# IF_RX.net
KiCad netlist of a schematic drawn in Altium Designer
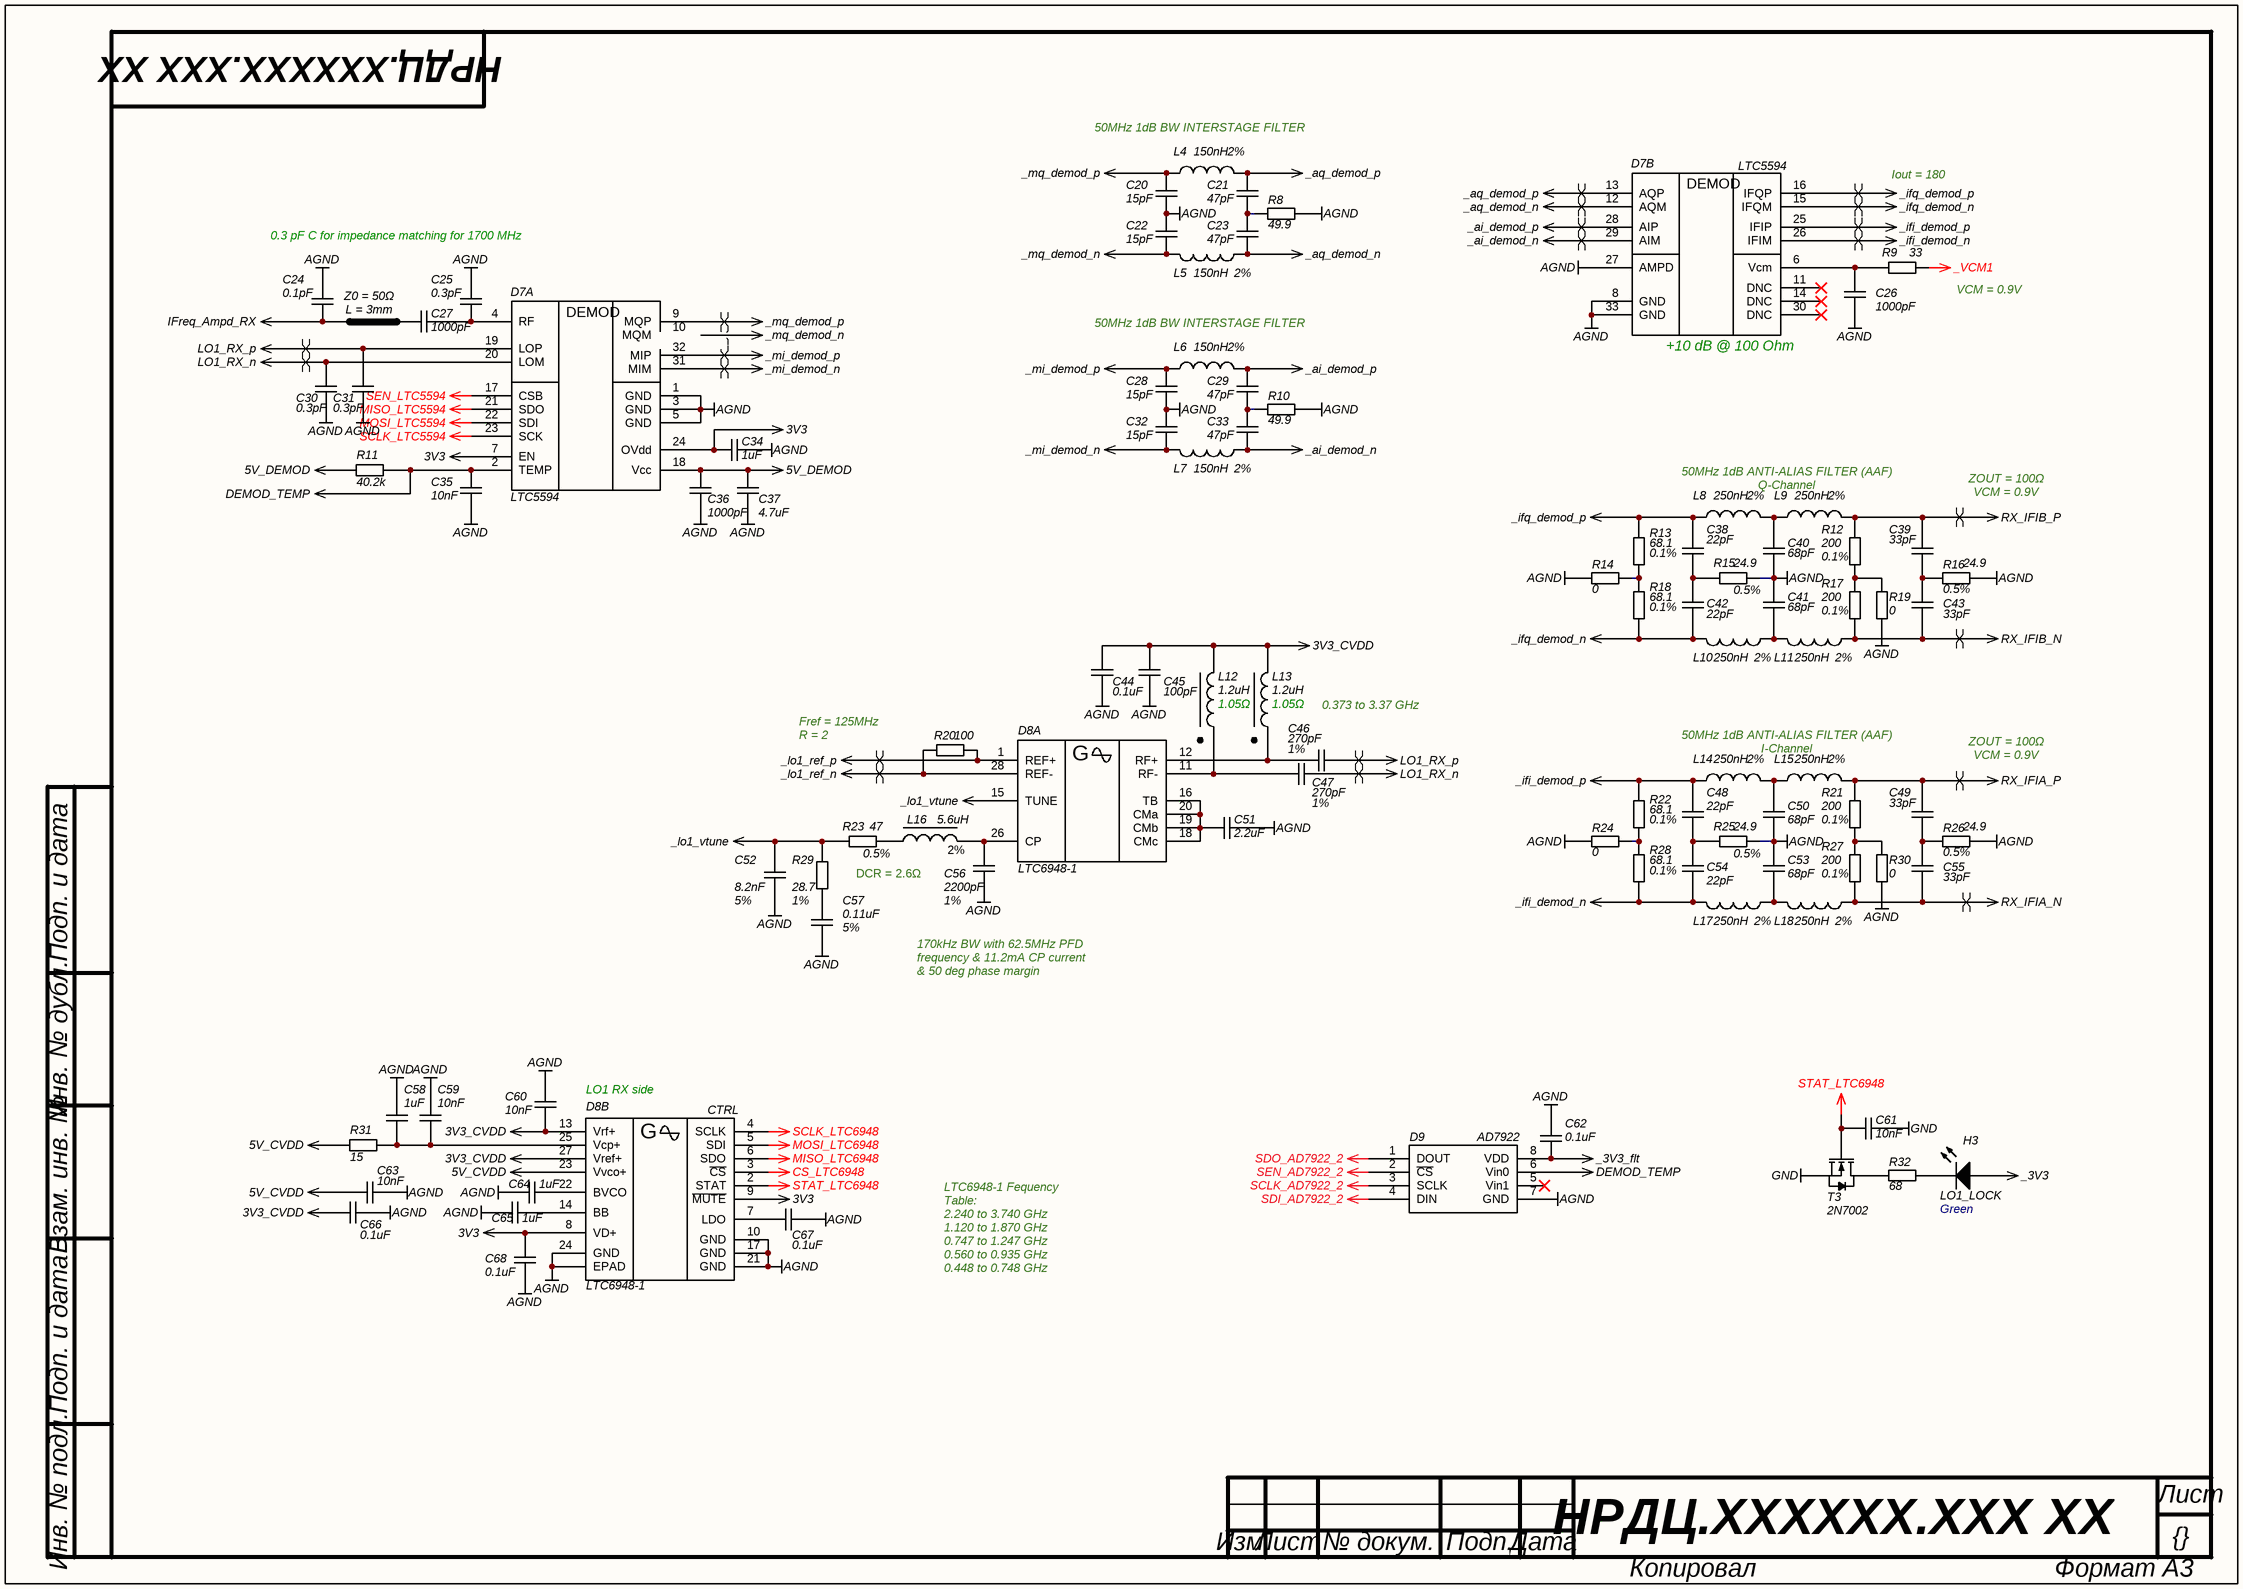
[diagram p0: IF_RX.SchDoc]

(export (version "E")
  (design (tool "Eeschema 10.0.6"))
  (components
    (comp (ref "C20")
      (value "15pF")
      (footprint "C0402")
      (description "SMD Capacitor")
      (fields (field (name "MANUFACTURER") "Murata") (field (name "TOLERANCE") "1%"))
      (libsource (lib "Kintex_SDR") (part "CAP"))
    )
    (comp (ref "C21")
      (value "47pF")
      (footprint "C0402")
      (description "SMD Capacitor")
      (fields (field (name "MANUFACTURER") "Murata") (field (name "TOLERANCE") "1%"))
      (libsource (lib "Kintex_SDR") (part "CAP"))
    )
    (comp (ref "C22")
      (value "15pF")
      (footprint "C0402")
      (description "SMD Capacitor")
      (fields (field (name "MANUFACTURER") "Murata") (field (name "TOLERANCE") "1%"))
      (libsource (lib "Kintex_SDR") (part "CAP"))
    )
    (comp (ref "C23")
      (value "47pF")
      (footprint "C0402")
      (description "SMD Capacitor")
      (fields (field (name "MANUFACTURER") "Murata") (field (name "TOLERANCE") "1%"))
      (libsource (lib "Kintex_SDR") (part "CAP"))
    )
    (comp (ref "C24")
      (value "0.1pF")
      (footprint "C0402")
      (description "SMD Capacitor")
      (fields (field (name "MANUFACTURER") "Murata") (field (name "TOLERANCE") "±0.05pF"))
      (libsource (lib "Kintex_SDR") (part "CAP"))
    )
    (comp (ref "C25")
      (value "0.3pF")
      (footprint "C0402")
      (description "SMD Capacitor")
      (fields (field (name "MANUFACTURER") "Murata") (field (name "TOLERANCE") "±0.05pF"))
      (libsource (lib "Kintex_SDR") (part "CAP"))
    )
    (comp (ref "C26")
      (value "1000pF")
      (footprint "C0402")
      (description "SMD Capacitor")
      (fields (field (name "MANUFACTURER") "Murata") (field (name "TOLERANCE") "5%"))
      (libsource (lib "Kintex_SDR") (part "CAP"))
    )
    (comp (ref "C27")
      (value "1000pF")
      (footprint "C0402")
      (description "SMD Capacitor")
      (fields (field (name "MANUFACTURER") "Murata") (field (name "TOLERANCE") "5%"))
      (libsource (lib "Kintex_SDR") (part "CAP"))
    )
    (comp (ref "C28")
      (value "15pF")
      (footprint "C0402")
      (description "SMD Capacitor")
      (fields (field (name "MANUFACTURER") "Murata") (field (name "TOLERANCE") "1%"))
      (libsource (lib "Kintex_SDR") (part "CAP"))
    )
    (comp (ref "C29")
      (value "47pF")
      (footprint "C0402")
      (description "SMD Capacitor")
      (fields (field (name "MANUFACTURER") "Murata") (field (name "TOLERANCE") "1%"))
      (libsource (lib "Kintex_SDR") (part "CAP"))
    )
    (comp (ref "C30")
      (value "0.3pF")
      (footprint "C0402")
      (description "SMD Capacitor")
      (fields (field (name "MANUFACTURER") "Murata") (field (name "TOLERANCE") "±0.05pF"))
      (libsource (lib "Kintex_SDR") (part "CAP"))
    )
    (comp (ref "C31")
      (value "0.3pF")
      (footprint "C0402")
      (description "SMD Capacitor")
      (fields (field (name "MANUFACTURER") "Murata") (field (name "TOLERANCE") "±0.05pF"))
      (libsource (lib "Kintex_SDR") (part "CAP"))
    )
    (comp (ref "C32")
      (value "15pF")
      (footprint "C0402")
      (description "SMD Capacitor")
      (fields (field (name "MANUFACTURER") "Murata") (field (name "TOLERANCE") "1%"))
      (libsource (lib "Kintex_SDR") (part "CAP"))
    )
    (comp (ref "C33")
      (value "47pF")
      (footprint "C0402")
      (description "SMD Capacitor")
      (fields (field (name "MANUFACTURER") "Murata") (field (name "TOLERANCE") "1%"))
      (libsource (lib "Kintex_SDR") (part "CAP"))
    )
    (comp (ref "C34")
      (value "1uF")
      (footprint "C0805")
      (description "SMD Capacitor")
      (fields (field (name "MANUFACTURER") "Murata") (field (name "TOLERANCE") "10%"))
      (libsource (lib "Kintex_SDR") (part "CAP"))
    )
    (comp (ref "C35")
      (value "10nF")
      (footprint "C0402")
      (description "SMD Capacitor")
      (fields (field (name "MANUFACTURER") "Murata") (field (name "TOLERANCE") "10%"))
      (libsource (lib "Kintex_SDR") (part "CAP"))
    )
    (comp (ref "C36")
      (value "1000pF")
      (footprint "C0402")
      (description "SMD Capacitor")
      (fields (field (name "MANUFACTURER") "Murata") (field (name "TOLERANCE") "5%"))
      (libsource (lib "Kintex_SDR") (part "CAP"))
    )
    (comp (ref "C37")
      (value "4.7uF")
      (footprint "C0805")
      (description "SMD Capacitor")
      (fields (field (name "MANUFACTURER") "Murata") (field (name "TOLERANCE") "10%"))
      (libsource (lib "Kintex_SDR") (part "CAP"))
    )
    (comp (ref "C38")
      (value "22pF")
      (footprint "C0402")
      (description "SMD Capacitor")
      (fields (field (name "MANUFACTURER") "Murata") (field (name "TOLERANCE") "1%"))
      (libsource (lib "Kintex_SDR") (part "CAP"))
    )
    (comp (ref "C39")
      (value "33pF")
      (footprint "C0402")
      (description "SMD Capacitor")
      (fields (field (name "MANUFACTURER") "Murata") (field (name "TOLERANCE") "1%"))
      (libsource (lib "Kintex_SDR") (part "CAP"))
    )
    (comp (ref "C40")
      (value "68pF")
      (footprint "C0402")
      (description "SMD Capacitor")
      (fields (field (name "MANUFACTURER") "Murata") (field (name "TOLERANCE") "1%"))
      (libsource (lib "Kintex_SDR") (part "CAP"))
    )
    (comp (ref "C41")
      (value "68pF")
      (footprint "C0402")
      (description "SMD Capacitor")
      (fields (field (name "MANUFACTURER") "Murata") (field (name "TOLERANCE") "1%"))
      (libsource (lib "Kintex_SDR") (part "CAP"))
    )
    (comp (ref "C42")
      (value "22pF")
      (footprint "C0402")
      (description "SMD Capacitor")
      (fields (field (name "MANUFACTURER") "Murata") (field (name "TOLERANCE") "1%"))
      (libsource (lib "Kintex_SDR") (part "CAP"))
    )
    (comp (ref "C43")
      (value "33pF")
      (footprint "C0402")
      (description "SMD Capacitor")
      (fields (field (name "MANUFACTURER") "Murata") (field (name "TOLERANCE") "1%"))
      (libsource (lib "Kintex_SDR") (part "CAP"))
    )
    (comp (ref "C44")
      (value "0.1uF")
      (footprint "C0402")
      (description "SMD Capacitor")
      (fields (field (name "MANUFACTURER") "Murata") (field (name "TOLERANCE") "10%"))
      (libsource (lib "Kintex_SDR") (part "CAP"))
    )
    (comp (ref "C45")
      (value "100pF")
      (footprint "C0402")
      (description "SMD Capacitor")
      (fields (field (name "MANUFACTURER") "Murata") (field (name "TOLERANCE") "1%"))
      (libsource (lib "Kintex_SDR") (part "CAP"))
    )
    (comp (ref "C46")
      (value "270pF")
      (footprint "C0402")
      (description "SMD Capacitor")
      (fields
        (field (name "MANUFACTURER") "Murata")
        (field (name "TOLERANCE") "1%")
        (field (name "VOLTAGE") "50V")
      )
      (libsource (lib "Kintex_SDR") (part "CAP"))
    )
    (comp (ref "C47")
      (value "270pF")
      (footprint "C0402")
      (description "SMD Capacitor")
      (fields
        (field (name "MANUFACTURER") "Murata")
        (field (name "TOLERANCE") "1%")
        (field (name "VOLTAGE") "50V")
      )
      (libsource (lib "Kintex_SDR") (part "CAP"))
    )
    (comp (ref "C48")
      (value "22pF")
      (footprint "C0402")
      (description "SMD Capacitor")
      (fields (field (name "MANUFACTURER") "Murata") (field (name "TOLERANCE") "1%"))
      (libsource (lib "Kintex_SDR") (part "CAP"))
    )
    (comp (ref "C49")
      (value "33pF")
      (footprint "C0402")
      (description "SMD Capacitor")
      (fields (field (name "MANUFACTURER") "Murata") (field (name "TOLERANCE") "1%"))
      (libsource (lib "Kintex_SDR") (part "CAP"))
    )
    (comp (ref "C50")
      (value "68pF")
      (footprint "C0402")
      (description "SMD Capacitor")
      (fields (field (name "MANUFACTURER") "Murata") (field (name "TOLERANCE") "1%"))
      (libsource (lib "Kintex_SDR") (part "CAP"))
    )
    (comp (ref "C51")
      (value "2.2uF")
      (footprint "C0603")
      (description "SMD Capacitor")
      (fields (field (name "MANUFACTURER") "Murata") (field (name "TOLERANCE") "10%"))
      (libsource (lib "Kintex_SDR") (part "CAP"))
    )
    (comp (ref "C52")
      (value "8.2nF")
      (footprint "C0603")
      (description "SMD Capacitor")
      (fields
        (field (name "MANUFACTURER") "Murata")
        (field (name "TOLERANCE") "5%")
        (field (name "VOLTAGE") "50V")
      )
      (libsource (lib "Kintex_SDR") (part "CAP"))
    )
    (comp (ref "C53")
      (value "68pF")
      (footprint "C0402")
      (description "SMD Capacitor")
      (fields (field (name "MANUFACTURER") "Murata") (field (name "TOLERANCE") "1%"))
      (libsource (lib "Kintex_SDR") (part "CAP"))
    )
    (comp (ref "C54")
      (value "22pF")
      (footprint "C0402")
      (description "SMD Capacitor")
      (fields (field (name "MANUFACTURER") "Murata") (field (name "TOLERANCE") "1%"))
      (libsource (lib "Kintex_SDR") (part "CAP"))
    )
    (comp (ref "C55")
      (value "33pF")
      (footprint "C0402")
      (description "SMD Capacitor")
      (fields (field (name "MANUFACTURER") "Murata") (field (name "TOLERANCE") "1%"))
      (libsource (lib "Kintex_SDR") (part "CAP"))
    )
    (comp (ref "C56")
      (value "2200pF")
      (footprint "C0603")
      (description "SMD Capacitor")
      (fields
        (field (name "MANUFACTURER") "Murata")
        (field (name "TOLERANCE") "1%")
        (field (name "VOLTAGE") "50V")
      )
      (libsource (lib "Kintex_SDR") (part "CAP"))
    )
    (comp (ref "C57")
      (value "0.11uF")
      (footprint "C0805")
      (description "SMD Capacitor")
      (fields
        (field (name "MANUFACTURER") "Murata")
        (field (name "TOLERANCE") "5%")
        (field (name "VOLTAGE") "50V")
      )
      (libsource (lib "Kintex_SDR") (part "CAP"))
    )
    (comp (ref "C58")
      (value "1uF")
      (footprint "C0805")
      (description "SMD Capacitor")
      (fields (field (name "MANUFACTURER") "Murata") (field (name "TOLERANCE") "10%"))
      (libsource (lib "Kintex_SDR") (part "CAP"))
    )
    (comp (ref "C59")
      (value "10nF")
      (footprint "C0402")
      (description "SMD Capacitor")
      (fields (field (name "MANUFACTURER") "Murata") (field (name "TOLERANCE") "10%"))
      (libsource (lib "Kintex_SDR") (part "CAP"))
    )
    (comp (ref "C60")
      (value "10nF")
      (footprint "C0402")
      (description "SMD Capacitor")
      (fields (field (name "MANUFACTURER") "Murata") (field (name "TOLERANCE") "10%"))
      (libsource (lib "Kintex_SDR") (part "CAP"))
    )
    (comp (ref "C61")
      (value "10nF")
      (footprint "C0402")
      (description "SMD Capacitor")
      (fields (field (name "MANUFACTURER") "Murata") (field (name "TOLERANCE") "10%"))
      (libsource (lib "Kintex_SDR") (part "CAP"))
    )
    (comp (ref "C62")
      (value "0.1uF")
      (footprint "C0402")
      (description "SMD Capacitor")
      (fields (field (name "MANUFACTURER") "Murata") (field (name "TOLERANCE") "10%"))
      (libsource (lib "Kintex_SDR") (part "CAP"))
    )
    (comp (ref "C63")
      (value "10nF")
      (footprint "C0402")
      (description "SMD Capacitor")
      (fields (field (name "MANUFACTURER") "Murata") (field (name "TOLERANCE") "10%"))
      (libsource (lib "Kintex_SDR") (part "CAP"))
    )
    (comp (ref "C64")
      (value "1uF")
      (footprint "C0805")
      (description "SMD Capacitor")
      (fields (field (name "MANUFACTURER") "Murata") (field (name "TOLERANCE") "10%"))
      (libsource (lib "Kintex_SDR") (part "CAP"))
    )
    (comp (ref "C65")
      (value "1uF")
      (footprint "C0805")
      (description "SMD Capacitor")
      (fields (field (name "MANUFACTURER") "Murata") (field (name "TOLERANCE") "10%"))
      (libsource (lib "Kintex_SDR") (part "CAP"))
    )
    (comp (ref "C66")
      (value "0.1uF")
      (footprint "C0402")
      (description "SMD Capacitor")
      (fields (field (name "MANUFACTURER") "Murata") (field (name "TOLERANCE") "10%"))
      (libsource (lib "Kintex_SDR") (part "CAP"))
    )
    (comp (ref "C67")
      (value "0.1uF")
      (footprint "C0402")
      (description "SMD Capacitor")
      (fields (field (name "MANUFACTURER") "Murata") (field (name "TOLERANCE") "10%"))
      (libsource (lib "Kintex_SDR") (part "CAP"))
    )
    (comp (ref "C68")
      (value "0.1uF")
      (footprint "C0402")
      (description "SMD Capacitor")
      (fields (field (name "MANUFACTURER") "Murata") (field (name "TOLERANCE") "10%"))
      (libsource (lib "Kintex_SDR") (part "CAP"))
    )
    (comp (ref "D7")
      (value "LTC5594")
      (footprint "DBLib:QFN-32")
      (description "Quadrature Demodulator")
      (fields (field (name "MANUFACTURER") "Analog Devices"))
      (libsource (lib "DBLib") (part "LTC5594"))
    )
    (comp (ref "D8")
      (value "LTC6948-1")
      (footprint "QFN-28")
      (description "The LTC®LTC6948 is a high performance, low noise, 6.39GHz  phase-locked loop (PLL)")
      (fields (field (name "MANUFACTURER") "Linear Technology") (field (name "VOLTAGE") "3.15 V ~ 5.25 V"))
      (libsource (lib "") (part "LTC6948_1"))
    )
    (comp (ref "D9")
      (value "AD7922")
      (footprint "MSOP-8")
      (description "1 MSPS, 10-/12-Bit ADC")
      (fields (field (name "MANUFACTURER") "Analog Device") (field (name "VOLTAGE") "2.35 V to 5.25 V"))
      (libsource (lib "Kintex_SDR") (part "AD79x2"))
    )
    (comp (ref "H3")
      (value "LO1_LOCK")
      (footprint "LED")
      (description "CHIP LED LAMP")
      (fields (field (name "MANUFACTURER") "Kingbright") (field (name "COLOR") "Green"))
      (libsource (lib "DBLib") (part "LED"))
    )
    (comp (ref "L4")
      (value "150nH")
      (footprint "DBLib:L0603_HP")
      (description "Chip SMD Inductor")
      (fields
        (field (name "MANUFACTURER") "Coilcraft")
        (field (name "TOLERANCE") "2%")
        (field (name "Comment") "Inductor RF")
      )
      (libsource (lib "") (part "Inductor RF_1"))
    )
    (comp (ref "L5")
      (value "150nH")
      (footprint "DBLib:L0603_HP")
      (description "Chip SMD Inductor")
      (fields
        (field (name "MANUFACTURER") "Coilcraft")
        (field (name "TOLERANCE") "2%")
        (field (name "Comment") "Inductor RF")
      )
      (libsource (lib "DBLib") (part "Inductor RF"))
    )
    (comp (ref "L6")
      (value "150nH")
      (footprint "DBLib:L0603_HP")
      (description "Chip SMD Inductor")
      (fields
        (field (name "MANUFACTURER") "Coilcraft")
        (field (name "TOLERANCE") "2%")
        (field (name "Comment") "Inductor RF")
      )
      (libsource (lib "") (part "Inductor RF_1"))
    )
    (comp (ref "L7")
      (value "150nH")
      (footprint "DBLib:L0603_HP")
      (description "Chip SMD Inductor")
      (fields
        (field (name "MANUFACTURER") "Coilcraft")
        (field (name "TOLERANCE") "2%")
        (field (name "Comment") "Inductor RF")
      )
      (libsource (lib "DBLib") (part "Inductor RF"))
    )
    (comp (ref "L8")
      (value "250nH")
      (footprint "DBLib:L0603_HP")
      (description "Chip SMD Inductor")
      (fields
        (field (name "MANUFACTURER") "Coilcraft")
        (field (name "TOLERANCE") "2%")
        (field (name "Comment") "Inductor RF")
      )
      (libsource (lib "") (part "Inductor RF_1"))
    )
    (comp (ref "L9")
      (value "250nH")
      (footprint "DBLib:L0603_HP")
      (description "Chip SMD Inductor")
      (fields
        (field (name "MANUFACTURER") "Coilcraft")
        (field (name "TOLERANCE") "2%")
        (field (name "Comment") "Inductor RF")
      )
      (libsource (lib "") (part "Inductor RF_1"))
    )
    (comp (ref "L10")
      (value "250nH")
      (footprint "DBLib:L0603_HP")
      (description "Chip SMD Inductor")
      (fields
        (field (name "MANUFACTURER") "Coilcraft")
        (field (name "TOLERANCE") "2%")
        (field (name "Comment") "Inductor RF")
      )
      (libsource (lib "DBLib") (part "Inductor RF"))
    )
    (comp (ref "L11")
      (value "250nH")
      (footprint "DBLib:L0603_HP")
      (description "Chip SMD Inductor")
      (fields
        (field (name "MANUFACTURER") "Coilcraft")
        (field (name "TOLERANCE") "2%")
        (field (name "Comment") "Inductor RF")
      )
      (libsource (lib "DBLib") (part "Inductor RF"))
    )
    (comp (ref "L12")
      (value "1.2uH")
      (footprint "DBLib:BCR-122")
      (description "Broadband Conical Inductor")
      (fields
        (field (name "MANUFACTURER") "Coilcraft")
        (field (name "TOLERANCE") "±5%")
        (field (name "DCR") "1.05Ω")
      )
      (libsource (lib "DBLib") (part "Inductor_BCR"))
    )
    (comp (ref "L13")
      (value "1.2uH")
      (footprint "DBLib:BCR-122")
      (description "Broadband Conical Inductor")
      (fields
        (field (name "MANUFACTURER") "Coilcraft")
        (field (name "TOLERANCE") "±5%")
        (field (name "DCR") "1.05Ω")
      )
      (libsource (lib "DBLib") (part "Inductor_BCR"))
    )
    (comp (ref "L14")
      (value "250nH")
      (footprint "DBLib:L0603_HP")
      (description "Chip SMD Inductor")
      (fields
        (field (name "MANUFACTURER") "Coilcraft")
        (field (name "TOLERANCE") "2%")
        (field (name "Comment") "Inductor RF")
      )
      (libsource (lib "") (part "Inductor RF_1"))
    )
    (comp (ref "L15")
      (value "250nH")
      (footprint "DBLib:L0603_HP")
      (description "Chip SMD Inductor")
      (fields
        (field (name "MANUFACTURER") "Coilcraft")
        (field (name "TOLERANCE") "2%")
        (field (name "Comment") "Inductor RF")
      )
      (libsource (lib "") (part "Inductor RF_1"))
    )
    (comp (ref "L16")
      (value "5.6uH")
      (footprint "DBLib:L0603_LS")
      (description "Chip SMD Inductor")
      (fields
        (field (name "MANUFACTURER") "Coilcraft")
        (field (name "TOLERANCE") "2%")
        (field (name "Comment") "Inductor")
      )
      (libsource (lib "DBLib") (part "Inductor"))
    )
    (comp (ref "L17")
      (value "250nH")
      (footprint "DBLib:L0603_HP")
      (description "Chip SMD Inductor")
      (fields
        (field (name "MANUFACTURER") "Coilcraft")
        (field (name "TOLERANCE") "2%")
        (field (name "Comment") "Inductor RF")
      )
      (libsource (lib "DBLib") (part "Inductor RF"))
    )
    (comp (ref "L18")
      (value "250nH")
      (footprint "DBLib:L0603_HP")
      (description "Chip SMD Inductor")
      (fields
        (field (name "MANUFACTURER") "Coilcraft")
        (field (name "TOLERANCE") "2%")
        (field (name "Comment") "Inductor RF")
      )
      (libsource (lib "DBLib") (part "Inductor RF"))
    )
    (comp (ref "R8")
      (value "49.9")
      (footprint "R0402")
      (description "SMD Resistor")
      (fields (field (name "POWER") "0.063 Wt") (field (name "TOLERANCE") "0.5%"))
      (libsource (lib "Kintex_SDR") (part "RES"))
    )
    (comp (ref "R9")
      (value "33")
      (footprint "R0603")
      (description "SMD Resistor")
      (fields (field (name "POWER") "0.1 Wt") (field (name "TOLERANCE") "1%"))
      (libsource (lib "") (part "RES_2"))
    )
    (comp (ref "R10")
      (value "49.9")
      (footprint "R0402")
      (description "SMD Resistor")
      (fields (field (name "POWER") "0.063 Wt") (field (name "TOLERANCE") "0.5%"))
      (libsource (lib "Kintex_SDR") (part "RES"))
    )
    (comp (ref "R11")
      (value "40.2k")
      (footprint "R0402")
      (description "SMD Resistor")
      (fields (field (name "POWER") "0.063 Wt") (field (name "TOLERANCE") "1%"))
      (libsource (lib "Kintex_SDR") (part "RES"))
    )
    (comp (ref "R12")
      (value "200")
      (footprint "R0402")
      (description "SMD Resistor")
      (fields
        (field (name "POWER") "0.063 Wt")
        (field (name "TOLERANCE") "0.1%")
        (field (name "MANUFACTURER") "Panasonic Electronic Components")
      )
      (libsource (lib "") (part "RES_1"))
    )
    (comp (ref "R13")
      (value "68.1")
      (footprint "R0402")
      (description "SMD Resistor")
      (fields
        (field (name "POWER") "0.063 Wt")
        (field (name "TOLERANCE") "0.1%")
        (field (name "MANUFACTURER") "Panasonic Electronic Components")
      )
      (libsource (lib "") (part "RES_1"))
    )
    (comp (ref "R14")
      (value "0")
      (footprint "R0603")
      (description "SMD Resistor")
      (fields (field (name "POWER") "0.1 Wt") (field (name "TOLERANCE") "1%"))
      (libsource (lib "Kintex_SDR") (part "RES"))
    )
    (comp (ref "R15")
      (value "24.9")
      (footprint "R0402")
      (description "SMD Resistor")
      (fields
        (field (name "POWER") "0.063 Wt")
        (field (name "TOLERANCE") "0.5%")
        (field (name "MANUFACTURER") "Panasonic Electronic Components")
      )
      (libsource (lib "Kintex_SDR") (part "RES"))
    )
    (comp (ref "R16")
      (value "24.9")
      (footprint "R0402")
      (description "SMD Resistor")
      (fields
        (field (name "POWER") "0.063 Wt")
        (field (name "TOLERANCE") "0.5%")
        (field (name "MANUFACTURER") "Panasonic Electronic Components")
      )
      (libsource (lib "Kintex_SDR") (part "RES"))
    )
    (comp (ref "R17")
      (value "200")
      (footprint "R0402")
      (description "SMD Resistor")
      (fields
        (field (name "POWER") "0.063 Wt")
        (field (name "TOLERANCE") "0.1%")
        (field (name "MANUFACTURER") "Panasonic Electronic Components")
      )
      (libsource (lib "") (part "RES_1"))
    )
    (comp (ref "R18")
      (value "68.1")
      (footprint "R0402")
      (description "SMD Resistor")
      (fields
        (field (name "POWER") "0.063 Wt")
        (field (name "TOLERANCE") "0.1%")
        (field (name "MANUFACTURER") "Panasonic Electronic Components")
      )
      (libsource (lib "") (part "RES_1"))
    )
    (comp (ref "R19")
      (value "0")
      (footprint "R0603")
      (description "SMD Resistor")
      (fields (field (name "POWER") "0.1 Wt") (field (name "TOLERANCE") "1%"))
      (libsource (lib "") (part "RES_1"))
    )
    (comp (ref "R20")
      (value "100")
      (footprint "R0402")
      (description "SMD Resistor")
      (fields (field (name "POWER") "0.062 Wt") (field (name "TOLERANCE") "5%"))
      (libsource (lib "Kintex_SDR") (part "RES"))
    )
    (comp (ref "R21")
      (value "200")
      (footprint "R0402")
      (description "SMD Resistor")
      (fields
        (field (name "POWER") "0.063 Wt")
        (field (name "TOLERANCE") "0.1%")
        (field (name "MANUFACTURER") "Panasonic Electronic Components")
      )
      (libsource (lib "") (part "RES_1"))
    )
    (comp (ref "R22")
      (value "68.1")
      (footprint "R0402")
      (description "SMD Resistor")
      (fields
        (field (name "POWER") "0.063 Wt")
        (field (name "TOLERANCE") "0.1%")
        (field (name "MANUFACTURER") "Panasonic Electronic Components")
      )
      (libsource (lib "") (part "RES_1"))
    )
    (comp (ref "R23")
      (value "47")
      (footprint "R0402")
      (description "SMD Resistor")
      (fields
        (field (name "POWER") "0.2 Wt")
        (field (name "TOLERANCE") "0.5%")
        (field (name "MANUFACTURER") "Panasonic Electronic Components")
      )
      (libsource (lib "") (part "RES_2"))
    )
    (comp (ref "R24")
      (value "0")
      (footprint "R0603")
      (description "SMD Resistor")
      (fields (field (name "POWER") "0.1 Wt") (field (name "TOLERANCE") "1%"))
      (libsource (lib "Kintex_SDR") (part "RES"))
    )
    (comp (ref "R25")
      (value "24.9")
      (footprint "R0402")
      (description "SMD Resistor")
      (fields
        (field (name "POWER") "0.063 Wt")
        (field (name "TOLERANCE") "0.5%")
        (field (name "MANUFACTURER") "Panasonic Electronic Components")
      )
      (libsource (lib "Kintex_SDR") (part "RES"))
    )
    (comp (ref "R26")
      (value "24.9")
      (footprint "R0402")
      (description "SMD Resistor")
      (fields
        (field (name "POWER") "0.063 Wt")
        (field (name "TOLERANCE") "0.5%")
        (field (name "MANUFACTURER") "Panasonic Electronic Components")
      )
      (libsource (lib "Kintex_SDR") (part "RES"))
    )
    (comp (ref "R27")
      (value "200")
      (footprint "R0402")
      (description "SMD Resistor")
      (fields
        (field (name "POWER") "0.063 Wt")
        (field (name "TOLERANCE") "0.1%")
        (field (name "MANUFACTURER") "Panasonic Electronic Components")
      )
      (libsource (lib "") (part "RES_1"))
    )
    (comp (ref "R28")
      (value "68.1")
      (footprint "R0402")
      (description "SMD Resistor")
      (fields
        (field (name "POWER") "0.063 Wt")
        (field (name "TOLERANCE") "0.1%")
        (field (name "MANUFACTURER") "Panasonic Electronic Components")
      )
      (libsource (lib "") (part "RES_1"))
    )
    (comp (ref "R29")
      (value "28.7")
      (footprint "R0402")
      (description "SMD Resistor")
      (fields
        (field (name "POWER") "0.2 Wt")
        (field (name "TOLERANCE") "1%")
        (field (name "MANUFACTURER") "Panasonic Electronic Components")
      )
      (libsource (lib "") (part "RES_1"))
    )
    (comp (ref "R30")
      (value "0")
      (footprint "R0603")
      (description "SMD Resistor")
      (fields (field (name "POWER") "0.1 Wt") (field (name "TOLERANCE") "1%"))
      (libsource (lib "") (part "RES_1"))
    )
    (comp (ref "R31")
      (value "15")
      (footprint "R0603")
      (description "SMD Resistor")
      (fields (field (name "POWER") "0.1 Wt") (field (name "TOLERANCE") "1%"))
      (libsource (lib "") (part "RES_2"))
    )
    (comp (ref "R32")
      (value "68")
      (footprint "R0402")
      (description "SMD Resistor")
      (fields (field (name "POWER") "0.062 Wt") (field (name "TOLERANCE") "5%"))
      (libsource (lib "Kintex_SDR") (part "RES"))
    )
    (comp (ref "T3")
      (value "2N7002")
      (footprint "SOT-23")
      (description "N-Channel MOSFET 2N7002")
      (fields (field (name "VOLTAGE") "60V"))
      (libsource (lib "Kintex_SDR") (part "2N7002"))
    )
  )
  (nets
    (net (code "1") (name "3V3") (class "Default")
      (node (ref "C34") (pin "1") (pinfunction "1_1") (pintype "passive"))
      (node (ref "C68") (pin "2") (pinfunction "2_2") (pintype "passive"))
      (node (ref "D7") (pin "24") (pinfunction "OVdd_24") (pintype "passive"))
      (node (ref "D7") (pin "7") (pinfunction "EN_7") (pintype "passive"))
      (node (ref "D8") (pin "8") (pinfunction "VD+_8") (pintype "passive"))
      (node (ref "D8") (pin "9") (pinfunction "~{MUTE}_9") (pintype "passive"))
    )
    (net (code "2") (name "3V3_CVDD") (class "Default")
      (node (ref "C44") (pin "2") (pinfunction "2_2") (pintype "passive"))
      (node (ref "C45") (pin "2") (pinfunction "2_2") (pintype "passive"))
      (node (ref "C60") (pin "2") (pinfunction "2_2") (pintype "passive"))
      (node (ref "C66") (pin "2") (pinfunction "2_2") (pintype "passive"))
      (node (ref "D8") (pin "13") (pinfunction "Vrf+_13") (pintype "passive"))
      (node (ref "D8") (pin "27") (pinfunction "Vref+_27") (pintype "passive"))
      (node (ref "L12") (pin "2") (pinfunction "2_2") (pintype "passive"))
      (node (ref "L13") (pin "2") (pinfunction "2_2") (pintype "passive"))
    )
    (net (code "3") (name "5V_CVDD") (class "Default")
      (node (ref "C63") (pin "1") (pinfunction "1_1") (pintype "passive"))
      (node (ref "D8") (pin "23") (pinfunction "Vvco+_23") (pintype "passive"))
      (node (ref "R31") (pin "2") (pinfunction "2_2") (pintype "passive"))
    )
    (net (code "4") (name "5V_DEMOD") (class "Default")
      (node (ref "C36") (pin "1") (pinfunction "1_1") (pintype "passive"))
      (node (ref "C37") (pin "2") (pinfunction "2_2") (pintype "passive"))
      (node (ref "D7") (pin "18") (pinfunction "Vcc_18") (pintype "passive"))
      (node (ref "R11") (pin "1") (pinfunction "1_1") (pintype "passive"))
    )
    (net (code "5") (name "AGND") (class "Default")
      (node (ref "C20") (pin "2") (pinfunction "2_2") (pintype "passive"))
      (node (ref "C22") (pin "1") (pinfunction "1_1") (pintype "passive"))
      (node (ref "C24") (pin "2") (pinfunction "2_2") (pintype "passive"))
      (node (ref "C25") (pin "1") (pinfunction "1_1") (pintype "passive"))
      (node (ref "C26") (pin "2") (pinfunction "2_2") (pintype "passive"))
      (node (ref "C28") (pin "2") (pinfunction "2_2") (pintype "passive"))
      (node (ref "C30") (pin "2") (pinfunction "2_2") (pintype "passive"))
      (node (ref "C31") (pin "2") (pinfunction "2_2") (pintype "passive"))
      (node (ref "C32") (pin "1") (pinfunction "1_1") (pintype "passive"))
      (node (ref "C34") (pin "2") (pinfunction "2_2") (pintype "passive"))
      (node (ref "C35") (pin "2") (pinfunction "2_2") (pintype "passive"))
      (node (ref "C36") (pin "2") (pinfunction "2_2") (pintype "passive"))
      (node (ref "C37") (pin "1") (pinfunction "1_1") (pintype "passive"))
      (node (ref "C40") (pin "2") (pinfunction "2_2") (pintype "passive"))
      (node (ref "C41") (pin "1") (pinfunction "1_1") (pintype "passive"))
      (node (ref "C44") (pin "1") (pinfunction "1_1") (pintype "passive"))
      (node (ref "C45") (pin "1") (pinfunction "1_1") (pintype "passive"))
      (node (ref "C50") (pin "2") (pinfunction "2_2") (pintype "passive"))
      (node (ref "C51") (pin "1") (pinfunction "1_1") (pintype "passive"))
      (node (ref "C52") (pin "1") (pinfunction "1_1") (pintype "passive"))
      (node (ref "C53") (pin "1") (pinfunction "1_1") (pintype "passive"))
      (node (ref "C56") (pin "1") (pinfunction "1_1") (pintype "passive"))
      (node (ref "C57") (pin "1") (pinfunction "1_1") (pintype "passive"))
      (node (ref "C58") (pin "1") (pinfunction "1_1") (pintype "passive"))
      (node (ref "C59") (pin "1") (pinfunction "1_1") (pintype "passive"))
      (node (ref "C60") (pin "1") (pinfunction "1_1") (pintype "passive"))
      (node (ref "C62") (pin "2") (pinfunction "2_2") (pintype "passive"))
      (node (ref "C63") (pin "2") (pinfunction "2_2") (pintype "passive"))
      (node (ref "C64") (pin "1") (pinfunction "1_1") (pintype "passive"))
      (node (ref "C65") (pin "2") (pinfunction "2_2") (pintype "passive"))
      (node (ref "C66") (pin "1") (pinfunction "1_1") (pintype "passive"))
      (node (ref "C67") (pin "1") (pinfunction "1_1") (pintype "passive"))
      (node (ref "C68") (pin "1") (pinfunction "1_1") (pintype "passive"))
      (node (ref "D7") (pin "1") (pinfunction "GND_1") (pintype "passive"))
      (node (ref "D7") (pin "27") (pinfunction "AMPD_27") (pintype "passive"))
      (node (ref "D7") (pin "3") (pinfunction "GND_3") (pintype "passive"))
      (node (ref "D7") (pin "33") (pinfunction "GND_33") (pintype "passive"))
      (node (ref "D7") (pin "5") (pinfunction "GND_5") (pintype "passive"))
      (node (ref "D7") (pin "8") (pinfunction "GND_8") (pintype "passive"))
      (node (ref "D8") (pin "10") (pinfunction "GND_10") (pintype "passive"))
      (node (ref "D8") (pin "17") (pinfunction "GND_17") (pintype "passive"))
      (node (ref "D8") (pin "21") (pinfunction "GND_21") (pintype "passive"))
      (node (ref "D8") (pin "24") (pinfunction "GND_24") (pintype "passive"))
      (node (ref "D8") (pin "29") (pinfunction "EPAD_29") (pintype "passive"))
      (node (ref "D9") (pin "7") (pinfunction "GND_7") (pintype "passive"))
      (node (ref "R10") (pin "2") (pinfunction "2_2") (pintype "passive"))
      (node (ref "R14") (pin "1") (pinfunction "1_1") (pintype "passive"))
      (node (ref "R15") (pin "2") (pinfunction "2_2") (pintype "passive"))
      (node (ref "R16") (pin "2") (pinfunction "2_2") (pintype "passive"))
      (node (ref "R19") (pin "2") (pinfunction "2_2") (pintype "passive"))
      (node (ref "R24") (pin "1") (pinfunction "1_1") (pintype "passive"))
      (node (ref "R25") (pin "2") (pinfunction "2_2") (pintype "passive"))
      (node (ref "R26") (pin "2") (pinfunction "2_2") (pintype "passive"))
      (node (ref "R30") (pin "2") (pinfunction "2_2") (pintype "passive"))
      (node (ref "R8") (pin "2") (pinfunction "2_2") (pintype "passive"))
    )
    (net (code "6") (name "CS_LTC6948") (class "Default")
      (node (ref "D8") (pin "3") (pinfunction "~{CS}_3") (pintype "passive"))
    )
    (net (code "7") (name "DEMOD_TEMP") (class "Default")
      (node (ref "C35") (pin "1") (pinfunction "1_1") (pintype "passive"))
      (node (ref "D7") (pin "2") (pinfunction "TEMP_2") (pintype "passive"))
      (node (ref "D9") (pin "6") (pinfunction "Vin0_6") (pintype "passive"))
      (node (ref "R11") (pin "2") (pinfunction "2_2") (pintype "passive"))
    )
    (net (code "8") (name "GND") (class "Default")
      (node (ref "C61") (pin "2") (pinfunction "2_2") (pintype "passive"))
      (node (ref "T3") (pin "2") (pinfunction "S_2") (pintype "passive"))
    )
    (net (code "9") (name "IFreq_Ampd_RX") (class "Default")
      (node (ref "C24") (pin "1") (pinfunction "1_1") (pintype "passive"))
      (node (ref "C27") (pin "2") (pinfunction "2_2") (pintype "passive"))
    )
    (net (code "10") (name "LO1_RX_n") (class "Default")
      (node (ref "C30") (pin "1") (pinfunction "1_1") (pintype "passive"))
      (node (ref "C47") (pin "2") (pinfunction "2_2") (pintype "passive"))
      (node (ref "D7") (pin "20") (pinfunction "LOM_20") (pintype "passive"))
    )
    (net (code "11") (name "LO1_RX_p") (class "Default")
      (node (ref "C31") (pin "1") (pinfunction "1_1") (pintype "passive"))
      (node (ref "C46") (pin "2") (pinfunction "2_2") (pintype "passive"))
      (node (ref "D7") (pin "19") (pinfunction "LOP_19") (pintype "passive"))
    )
    (net (code "12") (name "MISO_LTC5594") (class "Default")
      (node (ref "D7") (pin "21") (pinfunction "SDO_21") (pintype "passive"))
    )
    (net (code "13") (name "MISO_LTC6948") (class "Default")
      (node (ref "D8") (pin "6") (pinfunction "SDO_6") (pintype "passive"))
    )
    (net (code "14") (name "MOSI_LTC5594") (class "Default")
      (node (ref "D7") (pin "22") (pinfunction "SDI_22") (pintype "passive"))
    )
    (net (code "15") (name "MOSI_LTC6948") (class "Default")
      (node (ref "D8") (pin "5") (pinfunction "SDI_5") (pintype "passive"))
    )
    (net (code "16") (name "Net-(C21-Pad2)") (class "Default")
      (node (ref "C21") (pin "2") (pinfunction "2_2") (pintype "passive"))
      (node (ref "C23") (pin "1") (pinfunction "1_1") (pintype "passive"))
      (node (ref "R8") (pin "1") (pinfunction "1_1") (pintype "passive"))
    )
    (net (code "17") (name "Net-(C29-Pad2)") (class "Default")
      (node (ref "C29") (pin "2") (pinfunction "2_2") (pintype "passive"))
      (node (ref "C33") (pin "1") (pinfunction "1_1") (pintype "passive"))
      (node (ref "R10") (pin "1") (pinfunction "1_1") (pintype "passive"))
    )
    (net (code "18") (name "Net-(C38-Pad2)") (class "Default")
      (node (ref "C38") (pin "2") (pinfunction "2_2") (pintype "passive"))
      (node (ref "C42") (pin "1") (pinfunction "1_1") (pintype "passive"))
      (node (ref "R15") (pin "1") (pinfunction "1_1") (pintype "passive"))
    )
    (net (code "19") (name "Net-(C39-Pad2)") (class "Default")
      (node (ref "C39") (pin "2") (pinfunction "2_2") (pintype "passive"))
      (node (ref "C43") (pin "1") (pinfunction "1_1") (pintype "passive"))
      (node (ref "R16") (pin "1") (pinfunction "1_1") (pintype "passive"))
    )
    (net (code "20") (name "Net-(C40-Pad1)") (class "Default")
      (node (ref "C40") (pin "1") (pinfunction "1_1") (pintype "passive"))
      (node (ref "L8") (pin "2") (pinfunction "2_2") (pintype "passive"))
      (node (ref "L9") (pin "1") (pinfunction "1_1") (pintype "passive"))
    )
    (net (code "21") (name "Net-(C41-Pad2)") (class "Default")
      (node (ref "C41") (pin "2") (pinfunction "2_2") (pintype "passive"))
      (node (ref "L10") (pin "2") (pinfunction "2_2") (pintype "passive"))
      (node (ref "L11") (pin "1") (pinfunction "1_1") (pintype "passive"))
    )
    (net (code "22") (name "Net-(C48-Pad2)") (class "Default")
      (node (ref "C48") (pin "2") (pinfunction "2_2") (pintype "passive"))
      (node (ref "C54") (pin "1") (pinfunction "1_1") (pintype "passive"))
      (node (ref "R25") (pin "1") (pinfunction "1_1") (pintype "passive"))
    )
    (net (code "23") (name "Net-(C49-Pad2)") (class "Default")
      (node (ref "C49") (pin "2") (pinfunction "2_2") (pintype "passive"))
      (node (ref "C55") (pin "1") (pinfunction "1_1") (pintype "passive"))
      (node (ref "R26") (pin "1") (pinfunction "1_1") (pintype "passive"))
    )
    (net (code "24") (name "Net-(C50-Pad1)") (class "Default")
      (node (ref "C50") (pin "1") (pinfunction "1_1") (pintype "passive"))
      (node (ref "L14") (pin "2") (pinfunction "2_2") (pintype "passive"))
      (node (ref "L15") (pin "1") (pinfunction "1_1") (pintype "passive"))
    )
    (net (code "25") (name "Net-(C53-Pad2)") (class "Default")
      (node (ref "C53") (pin "2") (pinfunction "2_2") (pintype "passive"))
      (node (ref "L17") (pin "2") (pinfunction "2_2") (pintype "passive"))
      (node (ref "L18") (pin "1") (pinfunction "1_1") (pintype "passive"))
    )
    (net (code "26") (name "Net-(C57-Pad2)") (class "Default")
      (node (ref "C57") (pin "2") (pinfunction "2_2") (pintype "passive"))
      (node (ref "R29") (pin "2") (pinfunction "2_2") (pintype "passive"))
    )
    (net (code "27") (name "Net-(D7A-RF)") (class "Default")
      (node (ref "C25") (pin "2") (pinfunction "2_2") (pintype "passive"))
      (node (ref "C27") (pin "1") (pinfunction "1_1") (pintype "passive"))
      (node (ref "D7") (pin "4") (pinfunction "RF_4") (pintype "passive"))
    )
    (net (code "28") (name "Net-(D7B-Vcm)") (class "Default")
      (node (ref "C26") (pin "1") (pinfunction "1_1") (pintype "passive"))
      (node (ref "D7") (pin "6") (pinfunction "Vcm_6") (pintype "passive"))
      (node (ref "R9") (pin "2") (pinfunction "2_2") (pintype "passive"))
    )
    (net (code "29") (name "Net-(D8A-CMa)") (class "Default")
      (node (ref "C51") (pin "2") (pinfunction "2_2") (pintype "passive"))
      (node (ref "D8") (pin "16") (pinfunction "TB_16") (pintype "passive"))
      (node (ref "D8") (pin "18") (pinfunction "CMc_18") (pintype "passive"))
      (node (ref "D8") (pin "19") (pinfunction "CMb_19") (pintype "passive"))
      (node (ref "D8") (pin "20") (pinfunction "CMa_20") (pintype "passive"))
    )
    (net (code "30") (name "Net-(D8A-CP)") (class "Default")
      (node (ref "C56") (pin "2") (pinfunction "2_2") (pintype "passive"))
      (node (ref "D8") (pin "26") (pinfunction "CP_26") (pintype "passive"))
      (node (ref "L16") (pin "2") (pinfunction "2_2") (pintype "passive"))
    )
    (net (code "31") (name "Net-(D8A-RF+)") (class "Default")
      (node (ref "C46") (pin "1") (pinfunction "1_1") (pintype "passive"))
      (node (ref "D8") (pin "12") (pinfunction "RF+_12") (pintype "passive"))
      (node (ref "L13") (pin "1") (pinfunction "1_1") (pintype "passive"))
    )
    (net (code "32") (name "Net-(D8A-RF-)") (class "Default")
      (node (ref "C47") (pin "1") (pinfunction "1_1") (pintype "passive"))
      (node (ref "D8") (pin "11") (pinfunction "RF-_11") (pintype "passive"))
      (node (ref "L12") (pin "1") (pinfunction "1_1") (pintype "passive"))
    )
    (net (code "33") (name "Net-(D8B-BB)") (class "Default")
      (node (ref "C65") (pin "1") (pinfunction "1_1") (pintype "passive"))
      (node (ref "D8") (pin "14") (pinfunction "BB_14") (pintype "passive"))
    )
    (net (code "34") (name "Net-(D8B-BVCO)") (class "Default")
      (node (ref "C64") (pin "2") (pinfunction "2_2") (pintype "passive"))
      (node (ref "D8") (pin "22") (pinfunction "BVCO_22") (pintype "passive"))
    )
    (net (code "35") (name "Net-(D8B-LDO)") (class "Default")
      (node (ref "C67") (pin "2") (pinfunction "2_2") (pintype "passive"))
      (node (ref "D8") (pin "7") (pinfunction "LDO_7") (pintype "passive"))
    )
    (net (code "36") (name "Net-(D8B-Vcp+)") (class "Default")
      (node (ref "C58") (pin "2") (pinfunction "2_2") (pintype "passive"))
      (node (ref "C59") (pin "2") (pinfunction "2_2") (pintype "passive"))
      (node (ref "D8") (pin "25") (pinfunction "Vcp+_25") (pintype "passive"))
      (node (ref "R31") (pin "1") (pinfunction "1_1") (pintype "passive"))
    )
    (net (code "37") (name "Net-(H3-K)") (class "Default")
      (node (ref "H3") (pin "1") (pinfunction "K_1") (pintype "passive"))
      (node (ref "R32") (pin "2") (pinfunction "2_2") (pintype "passive"))
    )
    (net (code "38") (name "Net-(L16-Pad1)") (class "Default")
      (node (ref "L16") (pin "1") (pinfunction "1_1") (pintype "passive"))
      (node (ref "R23") (pin "1") (pinfunction "1_1") (pintype "passive"))
    )
    (net (code "39") (name "Net-(R12-Pad2)") (class "Default")
      (node (ref "R12") (pin "2") (pinfunction "2_2") (pintype "passive"))
      (node (ref "R17") (pin "1") (pinfunction "1_1") (pintype "passive"))
      (node (ref "R19") (pin "1") (pinfunction "1_1") (pintype "passive"))
    )
    (net (code "40") (name "Net-(R13-Pad2)") (class "Default")
      (node (ref "R13") (pin "2") (pinfunction "2_2") (pintype "passive"))
      (node (ref "R14") (pin "2") (pinfunction "2_2") (pintype "passive"))
      (node (ref "R18") (pin "1") (pinfunction "1_1") (pintype "passive"))
    )
    (net (code "41") (name "Net-(R21-Pad2)") (class "Default")
      (node (ref "R21") (pin "2") (pinfunction "2_2") (pintype "passive"))
      (node (ref "R27") (pin "1") (pinfunction "1_1") (pintype "passive"))
      (node (ref "R30") (pin "1") (pinfunction "1_1") (pintype "passive"))
    )
    (net (code "42") (name "Net-(R22-Pad2)") (class "Default")
      (node (ref "R22") (pin "2") (pinfunction "2_2") (pintype "passive"))
      (node (ref "R24") (pin "2") (pinfunction "2_2") (pintype "passive"))
      (node (ref "R28") (pin "1") (pinfunction "1_1") (pintype "passive"))
    )
    (net (code "43") (name "Net-(T3-D)") (class "Default")
      (node (ref "R32") (pin "1") (pinfunction "1_1") (pintype "passive"))
      (node (ref "T3") (pin "3") (pinfunction "D_3") (pintype "passive"))
    )
    (net (code "44") (name "RX_IFIA_N") (class "Default")
      (node (ref "C55") (pin "2") (pinfunction "2_2") (pintype "passive"))
      (node (ref "L18") (pin "2") (pinfunction "2_2") (pintype "passive"))
      (node (ref "R27") (pin "2") (pinfunction "2_2") (pintype "passive"))
    )
    (net (code "45") (name "RX_IFIA_P") (class "Default")
      (node (ref "C49") (pin "1") (pinfunction "1_1") (pintype "passive"))
      (node (ref "L15") (pin "2") (pinfunction "2_2") (pintype "passive"))
      (node (ref "R21") (pin "1") (pinfunction "1_1") (pintype "passive"))
    )
    (net (code "46") (name "RX_IFIB_N") (class "Default")
      (node (ref "C43") (pin "2") (pinfunction "2_2") (pintype "passive"))
      (node (ref "L11") (pin "2") (pinfunction "2_2") (pintype "passive"))
      (node (ref "R17") (pin "2") (pinfunction "2_2") (pintype "passive"))
    )
    (net (code "47") (name "RX_IFIB_P") (class "Default")
      (node (ref "C39") (pin "1") (pinfunction "1_1") (pintype "passive"))
      (node (ref "L9") (pin "2") (pinfunction "2_2") (pintype "passive"))
      (node (ref "R12") (pin "1") (pinfunction "1_1") (pintype "passive"))
    )
    (net (code "48") (name "SCLK_AD7922_2") (class "Default")
      (node (ref "D9") (pin "3") (pinfunction "SCLK_3") (pintype "passive"))
    )
    (net (code "49") (name "SCLK_LTC5594") (class "Default")
      (node (ref "D7") (pin "23") (pinfunction "SCK_23") (pintype "passive"))
    )
    (net (code "50") (name "SCLK_LTC6948") (class "Default")
      (node (ref "D8") (pin "4") (pinfunction "SCLK_4") (pintype "passive"))
    )
    (net (code "51") (name "SDI_AD7922_2") (class "Default")
      (node (ref "D9") (pin "4") (pinfunction "DIN_4") (pintype "passive"))
    )
    (net (code "52") (name "SDO_AD7922_2") (class "Default")
      (node (ref "D9") (pin "1") (pinfunction "DOUT_1") (pintype "passive"))
    )
    (net (code "53") (name "SEN_AD7922_2") (class "Default")
      (node (ref "D9") (pin "2") (pinfunction "~{CS}_2") (pintype "passive"))
    )
    (net (code "54") (name "SEN_LTC5594") (class "Default")
      (node (ref "D7") (pin "17") (pinfunction "CSB_17") (pintype "passive"))
    )
    (net (code "55") (name "STAT_LTC6948") (class "Default")
      (node (ref "C61") (pin "1") (pinfunction "1_1") (pintype "passive"))
      (node (ref "D8") (pin "2") (pinfunction "STAT_2") (pintype "passive"))
      (node (ref "T3") (pin "1") (pinfunction "G_1") (pintype "passive"))
    )
    (net (code "56") (name "_3V3") (class "Default")
      (node (ref "H3") (pin "2") (pinfunction "A_2") (pintype "passive"))
    )
    (net (code "57") (name "_3V3_flt") (class "Default")
      (node (ref "C62") (pin "1") (pinfunction "1_1") (pintype "passive"))
      (node (ref "D9") (pin "8") (pinfunction "VDD_8") (pintype "passive"))
    )
    (net (code "58") (name "_VCM1") (class "Default")
      (node (ref "R9") (pin "1") (pinfunction "1_1") (pintype "passive"))
    )
    (net (code "59") (name "_ai_demod_n") (class "Default")
      (node (ref "C33") (pin "2") (pinfunction "2_2") (pintype "passive"))
      (node (ref "D7") (pin "29") (pinfunction "AIM_29") (pintype "passive"))
      (node (ref "L7") (pin "2") (pinfunction "2_2") (pintype "passive"))
    )
    (net (code "60") (name "_ai_demod_p") (class "Default")
      (node (ref "C29") (pin "1") (pinfunction "1_1") (pintype "passive"))
      (node (ref "D7") (pin "28") (pinfunction "AIP_28") (pintype "passive"))
      (node (ref "L6") (pin "2") (pinfunction "2_2") (pintype "passive"))
    )
    (net (code "61") (name "_aq_demod_n") (class "Default")
      (node (ref "C23") (pin "2") (pinfunction "2_2") (pintype "passive"))
      (node (ref "D7") (pin "12") (pinfunction "AQM_12") (pintype "passive"))
      (node (ref "L5") (pin "2") (pinfunction "2_2") (pintype "passive"))
    )
    (net (code "62") (name "_aq_demod_p") (class "Default")
      (node (ref "C21") (pin "1") (pinfunction "1_1") (pintype "passive"))
      (node (ref "D7") (pin "13") (pinfunction "AQP_13") (pintype "passive"))
      (node (ref "L4") (pin "2") (pinfunction "2_2") (pintype "passive"))
    )
    (net (code "63") (name "_ifi_demod_n") (class "Default")
      (node (ref "C54") (pin "2") (pinfunction "2_2") (pintype "passive"))
      (node (ref "D7") (pin "26") (pinfunction "IFIM_26") (pintype "passive"))
      (node (ref "L17") (pin "1") (pinfunction "1_1") (pintype "passive"))
      (node (ref "R28") (pin "2") (pinfunction "2_2") (pintype "passive"))
    )
    (net (code "64") (name "_ifi_demod_p") (class "Default")
      (node (ref "C48") (pin "1") (pinfunction "1_1") (pintype "passive"))
      (node (ref "D7") (pin "25") (pinfunction "IFIP_25") (pintype "passive"))
      (node (ref "L14") (pin "1") (pinfunction "1_1") (pintype "passive"))
      (node (ref "R22") (pin "1") (pinfunction "1_1") (pintype "passive"))
    )
    (net (code "65") (name "_ifq_demod_n") (class "Default")
      (node (ref "C42") (pin "2") (pinfunction "2_2") (pintype "passive"))
      (node (ref "D7") (pin "15") (pinfunction "IFQM_15") (pintype "passive"))
      (node (ref "L10") (pin "1") (pinfunction "1_1") (pintype "passive"))
      (node (ref "R18") (pin "2") (pinfunction "2_2") (pintype "passive"))
    )
    (net (code "66") (name "_ifq_demod_p") (class "Default")
      (node (ref "C38") (pin "1") (pinfunction "1_1") (pintype "passive"))
      (node (ref "D7") (pin "16") (pinfunction "IFQP_16") (pintype "passive"))
      (node (ref "L8") (pin "1") (pinfunction "1_1") (pintype "passive"))
      (node (ref "R13") (pin "1") (pinfunction "1_1") (pintype "passive"))
    )
    (net (code "67") (name "_lo1_ref_n") (class "Default")
      (node (ref "D8") (pin "28") (pinfunction "REF-_28") (pintype "passive"))
      (node (ref "R20") (pin "1") (pinfunction "1_1") (pintype "passive"))
    )
    (net (code "68") (name "_lo1_ref_p") (class "Default")
      (node (ref "D8") (pin "1") (pinfunction "REF+_1") (pintype "passive"))
      (node (ref "R20") (pin "2") (pinfunction "2_2") (pintype "passive"))
    )
    (net (code "69") (name "_lo1_vtune") (class "Default")
      (node (ref "C52") (pin "2") (pinfunction "2_2") (pintype "passive"))
      (node (ref "D8") (pin "15") (pinfunction "TUNE_15") (pintype "passive"))
      (node (ref "R23") (pin "2") (pinfunction "2_2") (pintype "passive"))
      (node (ref "R29") (pin "1") (pinfunction "1_1") (pintype "passive"))
    )
    (net (code "70") (name "_mi_demod_n") (class "Default")
      (node (ref "C32") (pin "2") (pinfunction "2_2") (pintype "passive"))
      (node (ref "D7") (pin "31") (pinfunction "MIM_31") (pintype "passive"))
      (node (ref "L7") (pin "1") (pinfunction "1_1") (pintype "passive"))
    )
    (net (code "71") (name "_mi_demod_p") (class "Default")
      (node (ref "C28") (pin "1") (pinfunction "1_1") (pintype "passive"))
      (node (ref "D7") (pin "32") (pinfunction "MIP_32") (pintype "passive"))
      (node (ref "L6") (pin "1") (pinfunction "1_1") (pintype "passive"))
    )
    (net (code "72") (name "_mq_demod_n") (class "Default")
      (node (ref "C22") (pin "2") (pinfunction "2_2") (pintype "passive"))
      (node (ref "D7") (pin "10") (pinfunction "MQM_10") (pintype "passive"))
      (node (ref "L5") (pin "1") (pinfunction "1_1") (pintype "passive"))
    )
    (net (code "73") (name "_mq_demod_p") (class "Default")
      (node (ref "C20") (pin "1") (pinfunction "1_1") (pintype "passive"))
      (node (ref "D7") (pin "9") (pinfunction "MQP_9") (pintype "passive"))
      (node (ref "L4") (pin "1") (pinfunction "1_1") (pintype "passive"))
    )
    (net (code "74") (name "unconnected-(D7B-DNC-Pad11)") (class "Default")
      (node (ref "D7") (pin "11") (pinfunction "DNC_11") (pintype "passive+no_connect"))
    )
    (net (code "75") (name "unconnected-(D7B-DNC-Pad14)") (class "Default")
      (node (ref "D7") (pin "14") (pinfunction "DNC_14") (pintype "passive+no_connect"))
    )
    (net (code "76") (name "unconnected-(D7B-DNC-Pad30)") (class "Default")
      (node (ref "D7") (pin "30") (pinfunction "DNC_30") (pintype "passive+no_connect"))
    )
    (net (code "77") (name "unconnected-(D9-Vin1-Pad5)") (class "Default")
      (node (ref "D9") (pin "5") (pinfunction "Vin1_5") (pintype "passive+no_connect"))
    )
  )
)
